# 8-Bit_Register_New.net
KiCad netlist of a schematic drawn in EAGLE
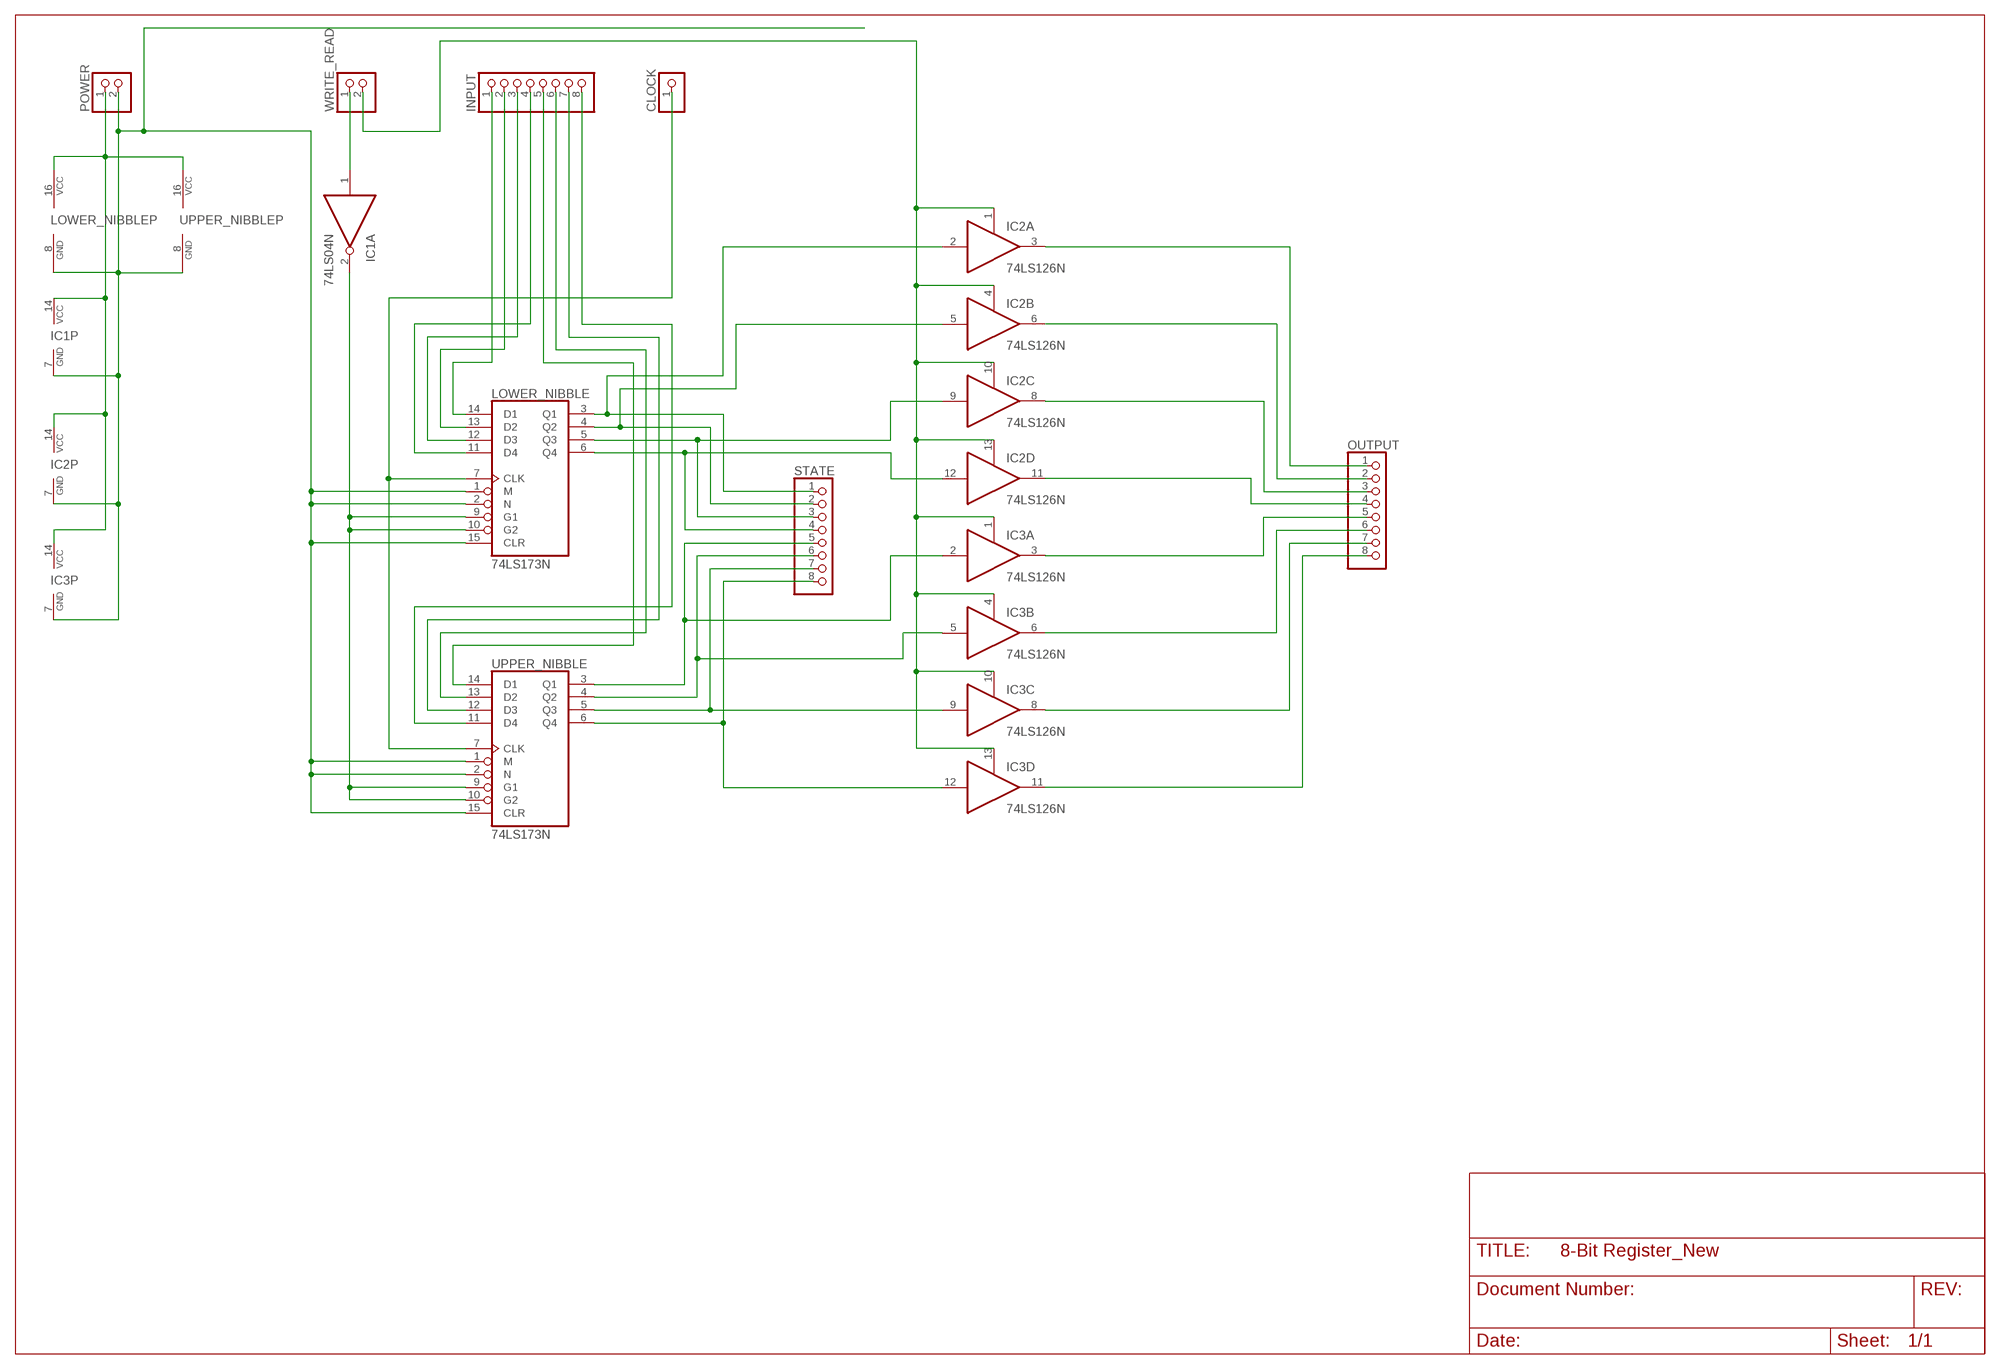
[diagram p0: schematic, sheet 1]

(export (version "E")
  (design (tool "Eeschema 10.0.6"))
  (components
    (comp (ref "CLOCK")
      (value "PINHD-1X1")
      (footprint "eagle-import:1X01")
      (libsource (lib "eagle-import") (part "PINHD-1X1"))
    )
    (comp (ref "IC1")
      (value "74LS04N")
      (footprint "eagle-import:DIL14")
      (libsource (lib "eagle-import") (part "7404NLS"))
    )
    (comp (ref "IC2")
      (value "74LS126N")
      (footprint "eagle-import:DIL14")
      (libsource (lib "eagle-import") (part "74126NLS"))
    )
    (comp (ref "IC3")
      (value "74LS126N")
      (footprint "eagle-import:DIL14")
      (libsource (lib "eagle-import") (part "74126NLS"))
    )
    (comp (ref "INPUT")
      (value "PINHD-1X8")
      (footprint "eagle-import:1X08")
      (libsource (lib "eagle-import") (part "PINHD-1X8"))
    )
    (comp (ref "LOWER_NIBBLE")
      (value "74LS173N")
      (footprint "eagle-import:DIL16")
      (libsource (lib "eagle-import") (part "74173NLS"))
    )
    (comp (ref "OUTPUT")
      (value "PINHD-1X8")
      (footprint "eagle-import:1X08")
      (libsource (lib "eagle-import") (part "PINHD-1X8"))
    )
    (comp (ref "POWER")
      (value "PINHD-1X2")
      (footprint "eagle-import:1X02")
      (libsource (lib "eagle-import") (part "PINHD-1X2"))
    )
    (comp (ref "STATE")
      (value "PINHD-1X8")
      (footprint "eagle-import:1X08")
      (libsource (lib "eagle-import") (part "PINHD-1X8"))
    )
    (comp (ref "UPPER_NIBBLE")
      (value "74LS173N")
      (footprint "eagle-import:DIL16")
      (libsource (lib "eagle-import") (part "74173NLS"))
    )
    (comp (ref "WRITE_READ")
      (value "PINHD-1X2")
      (footprint "eagle-import:1X02")
      (libsource (lib "eagle-import") (part "PINHD-1X2"))
    )
  )
  (nets
    (net (code "1") (name "Net-(IC1A-I)") (class "Default")
      (node (ref "IC1") (pin "1") (pinfunction "I_1") (pintype "input"))
      (node (ref "WRITE_READ") (pin "1") (pinfunction "1_1") (pintype "passive"))
    )
    (net (code "2") (name "Net-(IC1A-O)") (class "Default")
      (node (ref "IC1") (pin "2") (pinfunction "O_2") (pintype "output"))
      (node (ref "LOWER_NIBBLE") (pin "10") (pinfunction "G2_10") (pintype "input"))
      (node (ref "LOWER_NIBBLE") (pin "9") (pinfunction "G1_9") (pintype "input"))
      (node (ref "UPPER_NIBBLE") (pin "10") (pinfunction "G2_10") (pintype "input"))
      (node (ref "UPPER_NIBBLE") (pin "9") (pinfunction "G1_9") (pintype "input"))
    )
    (net (code "3") (name "Net-(IC1G-GND)") (class "Default")
      (node (ref "IC1") (pin "7") (pinfunction "GND_7") (pintype "power_in"))
      (node (ref "IC2") (pin "7") (pinfunction "GND_7") (pintype "power_in"))
      (node (ref "IC3") (pin "7") (pinfunction "GND_7") (pintype "power_in"))
      (node (ref "LOWER_NIBBLE") (pin "1") (pinfunction "M_1") (pintype "input"))
      (node (ref "LOWER_NIBBLE") (pin "15") (pinfunction "CLR_15") (pintype "input"))
      (node (ref "LOWER_NIBBLE") (pin "2") (pinfunction "N_2") (pintype "input"))
      (node (ref "LOWER_NIBBLE") (pin "8") (pinfunction "GND_8") (pintype "power_in"))
      (node (ref "POWER") (pin "2") (pinfunction "2_2") (pintype "passive"))
      (node (ref "UPPER_NIBBLE") (pin "1") (pinfunction "M_1") (pintype "input"))
      (node (ref "UPPER_NIBBLE") (pin "15") (pinfunction "CLR_15") (pintype "input"))
      (node (ref "UPPER_NIBBLE") (pin "2") (pinfunction "N_2") (pintype "input"))
      (node (ref "UPPER_NIBBLE") (pin "8") (pinfunction "GND_8") (pintype "power_in"))
    )
    (net (code "4") (name "Net-(IC1G-VCC)") (class "Default")
      (node (ref "IC1") (pin "14") (pinfunction "VCC_14") (pintype "power_in"))
      (node (ref "IC2") (pin "14") (pinfunction "VCC_14") (pintype "power_in"))
      (node (ref "IC3") (pin "14") (pinfunction "VCC_14") (pintype "power_in"))
      (node (ref "LOWER_NIBBLE") (pin "16") (pinfunction "VCC_16") (pintype "power_in"))
      (node (ref "POWER") (pin "1") (pinfunction "1_1") (pintype "passive"))
      (node (ref "UPPER_NIBBLE") (pin "16") (pinfunction "VCC_16") (pintype "power_in"))
    )
    (net (code "5") (name "Net-(IC2A-I)") (class "Default")
      (node (ref "IC2") (pin "2") (pinfunction "I_2") (pintype "input"))
      (node (ref "LOWER_NIBBLE") (pin "3") (pinfunction "Q1_3") (pintype "tri_state"))
      (node (ref "STATE") (pin "1") (pinfunction "1_1") (pintype "passive"))
    )
    (net (code "6") (name "Net-(IC2A-O)") (class "Default")
      (node (ref "IC2") (pin "3") (pinfunction "O_3") (pintype "output"))
      (node (ref "OUTPUT") (pin "1") (pinfunction "1_1") (pintype "passive"))
    )
    (net (code "7") (name "Net-(IC2A-OE)") (class "Default")
      (node (ref "IC2") (pin "1") (pinfunction "OE_1") (pintype "input"))
      (node (ref "IC2") (pin "10") (pinfunction "OE_10") (pintype "input"))
      (node (ref "IC2") (pin "13") (pinfunction "OE_13") (pintype "input"))
      (node (ref "IC2") (pin "4") (pinfunction "OE_4") (pintype "input"))
      (node (ref "IC3") (pin "1") (pinfunction "OE_1") (pintype "input"))
      (node (ref "IC3") (pin "10") (pinfunction "OE_10") (pintype "input"))
      (node (ref "IC3") (pin "13") (pinfunction "OE_13") (pintype "input"))
      (node (ref "IC3") (pin "4") (pinfunction "OE_4") (pintype "input"))
      (node (ref "WRITE_READ") (pin "2") (pinfunction "2_2") (pintype "passive"))
    )
    (net (code "8") (name "Net-(IC2B-I)") (class "Default")
      (node (ref "IC2") (pin "5") (pinfunction "I_5") (pintype "input"))
      (node (ref "LOWER_NIBBLE") (pin "4") (pinfunction "Q2_4") (pintype "tri_state"))
      (node (ref "STATE") (pin "2") (pinfunction "2_2") (pintype "passive"))
    )
    (net (code "9") (name "Net-(IC2B-O)") (class "Default")
      (node (ref "IC2") (pin "6") (pinfunction "O_6") (pintype "output"))
      (node (ref "OUTPUT") (pin "2") (pinfunction "2_2") (pintype "passive"))
    )
    (net (code "10") (name "Net-(IC2C-I)") (class "Default")
      (node (ref "IC2") (pin "9") (pinfunction "I_9") (pintype "input"))
      (node (ref "LOWER_NIBBLE") (pin "5") (pinfunction "Q3_5") (pintype "tri_state"))
      (node (ref "STATE") (pin "3") (pinfunction "3_3") (pintype "passive"))
    )
    (net (code "11") (name "Net-(IC2C-O)") (class "Default")
      (node (ref "IC2") (pin "8") (pinfunction "O_8") (pintype "output"))
      (node (ref "OUTPUT") (pin "3") (pinfunction "3_3") (pintype "passive"))
    )
    (net (code "12") (name "Net-(IC2D-I)") (class "Default")
      (node (ref "IC2") (pin "12") (pinfunction "I_12") (pintype "input"))
      (node (ref "LOWER_NIBBLE") (pin "6") (pinfunction "Q4_6") (pintype "tri_state"))
      (node (ref "STATE") (pin "4") (pinfunction "4_4") (pintype "passive"))
    )
    (net (code "13") (name "Net-(IC2D-O)") (class "Default")
      (node (ref "IC2") (pin "11") (pinfunction "O_11") (pintype "output"))
      (node (ref "OUTPUT") (pin "4") (pinfunction "4_4") (pintype "passive"))
    )
    (net (code "14") (name "Net-(IC3A-I)") (class "Default")
      (node (ref "IC3") (pin "2") (pinfunction "I_2") (pintype "input"))
      (node (ref "STATE") (pin "5") (pinfunction "5_5") (pintype "passive"))
      (node (ref "UPPER_NIBBLE") (pin "3") (pinfunction "Q1_3") (pintype "tri_state"))
    )
    (net (code "15") (name "Net-(IC3A-O)") (class "Default")
      (node (ref "IC3") (pin "3") (pinfunction "O_3") (pintype "output"))
      (node (ref "OUTPUT") (pin "5") (pinfunction "5_5") (pintype "passive"))
    )
    (net (code "16") (name "Net-(IC3B-I)") (class "Default")
      (node (ref "IC3") (pin "5") (pinfunction "I_5") (pintype "input"))
      (node (ref "STATE") (pin "6") (pinfunction "6_6") (pintype "passive"))
      (node (ref "UPPER_NIBBLE") (pin "4") (pinfunction "Q2_4") (pintype "tri_state"))
    )
    (net (code "17") (name "Net-(IC3B-O)") (class "Default")
      (node (ref "IC3") (pin "6") (pinfunction "O_6") (pintype "output"))
      (node (ref "OUTPUT") (pin "6") (pinfunction "6_6") (pintype "passive"))
    )
    (net (code "18") (name "Net-(IC3C-I)") (class "Default")
      (node (ref "IC3") (pin "9") (pinfunction "I_9") (pintype "input"))
      (node (ref "STATE") (pin "7") (pinfunction "7_7") (pintype "passive"))
      (node (ref "UPPER_NIBBLE") (pin "5") (pinfunction "Q3_5") (pintype "tri_state"))
    )
    (net (code "19") (name "Net-(IC3C-O)") (class "Default")
      (node (ref "IC3") (pin "8") (pinfunction "O_8") (pintype "output"))
      (node (ref "OUTPUT") (pin "7") (pinfunction "7_7") (pintype "passive"))
    )
    (net (code "20") (name "Net-(IC3D-I)") (class "Default")
      (node (ref "IC3") (pin "12") (pinfunction "I_12") (pintype "input"))
      (node (ref "STATE") (pin "8") (pinfunction "8_8") (pintype "passive"))
      (node (ref "UPPER_NIBBLE") (pin "6") (pinfunction "Q4_6") (pintype "tri_state"))
    )
    (net (code "21") (name "Net-(IC3D-O)") (class "Default")
      (node (ref "IC3") (pin "11") (pinfunction "O_11") (pintype "output"))
      (node (ref "OUTPUT") (pin "8") (pinfunction "8_8") (pintype "passive"))
    )
    (net (code "22") (name "Net-(LOWER_NIBBLEA-CLK)") (class "Default")
      (node (ref "CLOCK") (pin "1") (pinfunction "1_1") (pintype "passive"))
      (node (ref "LOWER_NIBBLE") (pin "7") (pinfunction "CLK_7") (pintype "input"))
      (node (ref "UPPER_NIBBLE") (pin "7") (pinfunction "CLK_7") (pintype "input"))
    )
    (net (code "23") (name "Net-(LOWER_NIBBLEA-D1)") (class "Default")
      (node (ref "INPUT") (pin "1") (pinfunction "1_1") (pintype "passive"))
      (node (ref "LOWER_NIBBLE") (pin "14") (pinfunction "D1_14") (pintype "input"))
    )
    (net (code "24") (name "Net-(LOWER_NIBBLEA-D2)") (class "Default")
      (node (ref "INPUT") (pin "2") (pinfunction "2_2") (pintype "passive"))
      (node (ref "LOWER_NIBBLE") (pin "13") (pinfunction "D2_13") (pintype "input"))
    )
    (net (code "25") (name "Net-(LOWER_NIBBLEA-D3)") (class "Default")
      (node (ref "INPUT") (pin "3") (pinfunction "3_3") (pintype "passive"))
      (node (ref "LOWER_NIBBLE") (pin "12") (pinfunction "D3_12") (pintype "input"))
    )
    (net (code "26") (name "Net-(LOWER_NIBBLEA-D4)") (class "Default")
      (node (ref "INPUT") (pin "4") (pinfunction "4_4") (pintype "passive"))
      (node (ref "LOWER_NIBBLE") (pin "11") (pinfunction "D4_11") (pintype "input"))
    )
    (net (code "27") (name "Net-(UPPER_NIBBLEA-D1)") (class "Default")
      (node (ref "INPUT") (pin "5") (pinfunction "5_5") (pintype "passive"))
      (node (ref "UPPER_NIBBLE") (pin "14") (pinfunction "D1_14") (pintype "input"))
    )
    (net (code "28") (name "Net-(UPPER_NIBBLEA-D2)") (class "Default")
      (node (ref "INPUT") (pin "6") (pinfunction "6_6") (pintype "passive"))
      (node (ref "UPPER_NIBBLE") (pin "13") (pinfunction "D2_13") (pintype "input"))
    )
    (net (code "29") (name "Net-(UPPER_NIBBLEA-D3)") (class "Default")
      (node (ref "INPUT") (pin "7") (pinfunction "7_7") (pintype "passive"))
      (node (ref "UPPER_NIBBLE") (pin "12") (pinfunction "D3_12") (pintype "input"))
    )
    (net (code "30") (name "Net-(UPPER_NIBBLEA-D4)") (class "Default")
      (node (ref "INPUT") (pin "8") (pinfunction "8_8") (pintype "passive"))
      (node (ref "UPPER_NIBBLE") (pin "11") (pinfunction "D4_11") (pintype "input"))
    )
  )
)
